# version1_4.net
KiCad netlist of a schematic drawn in EAGLE
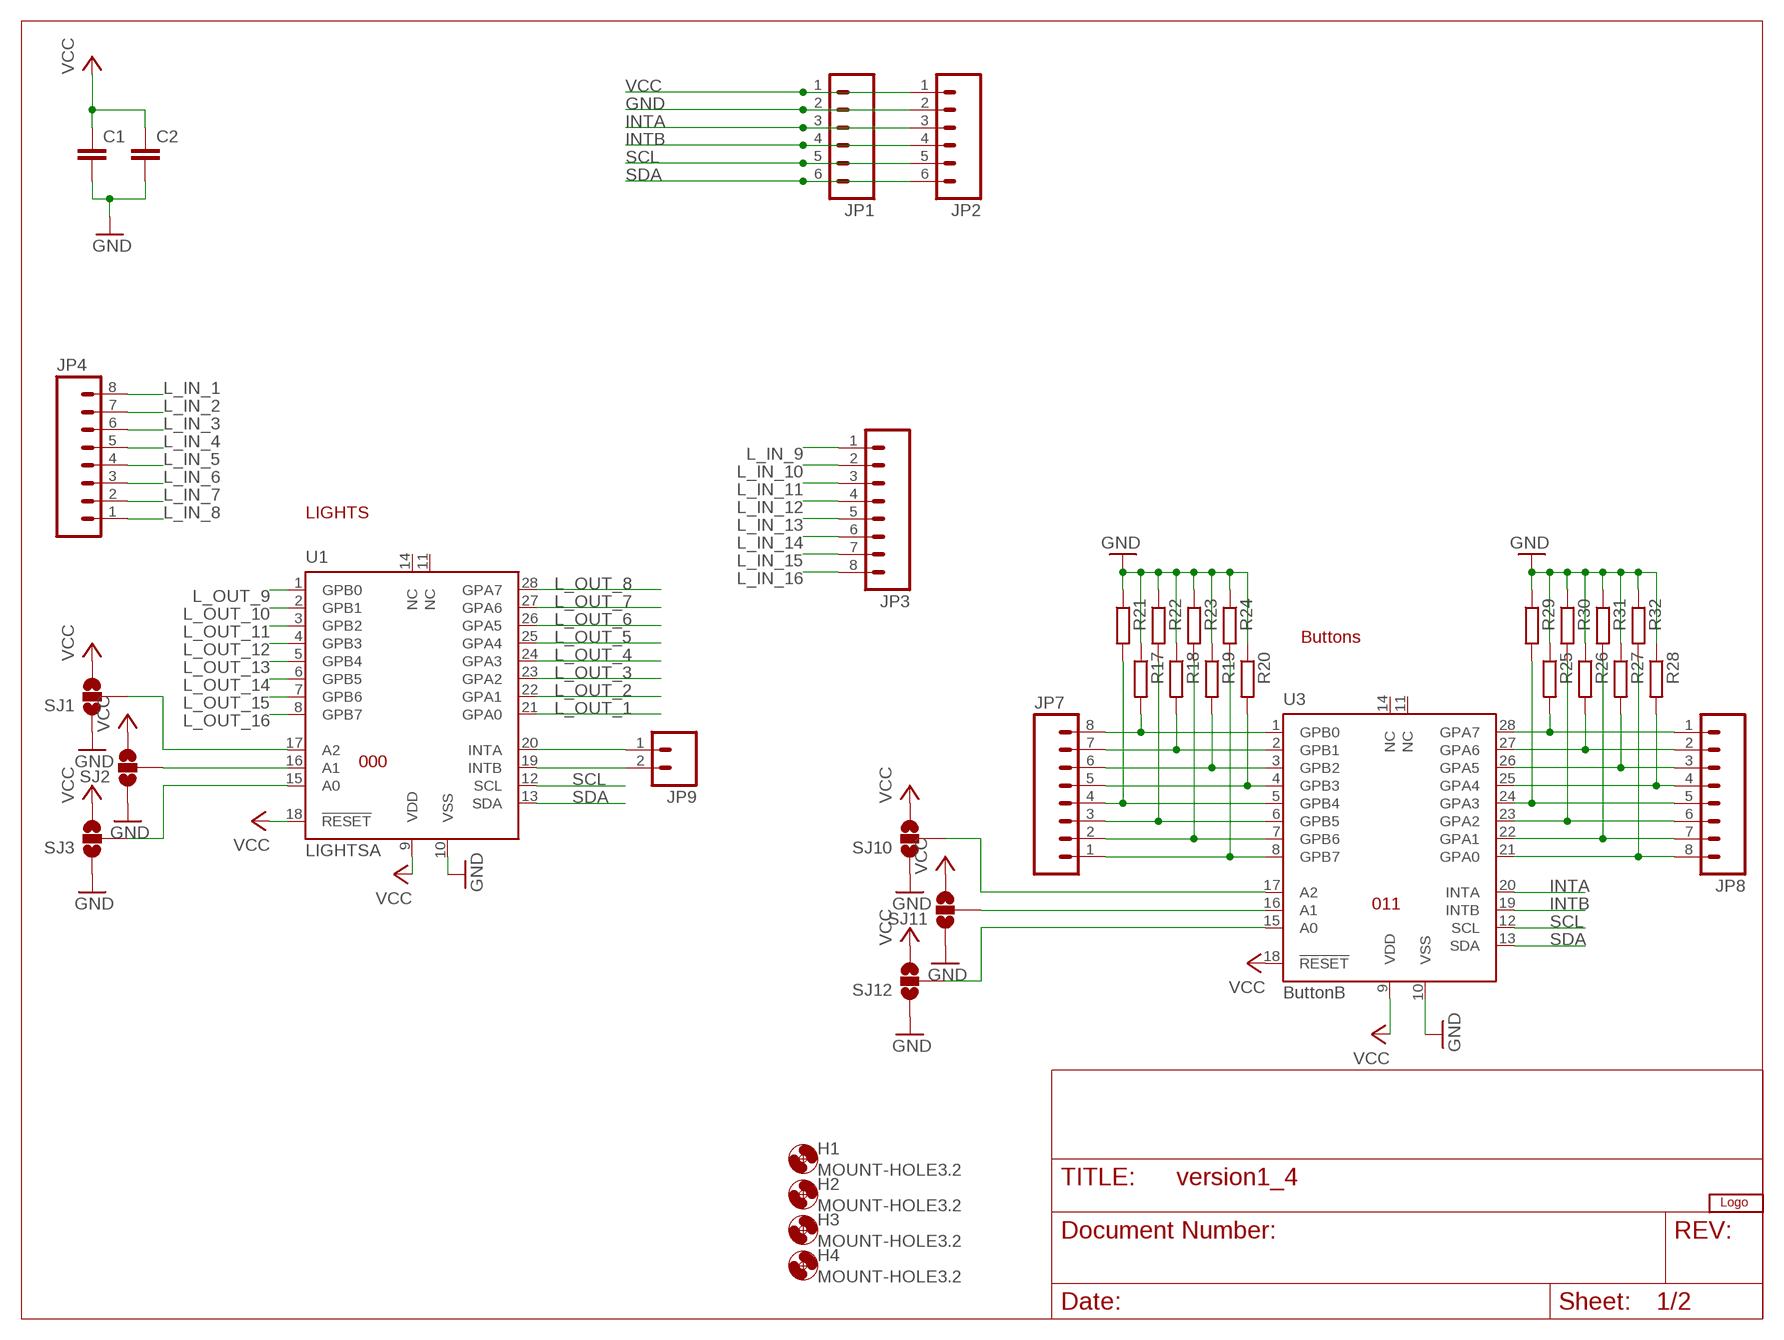
[diagram p0: schematic, sheet 1]
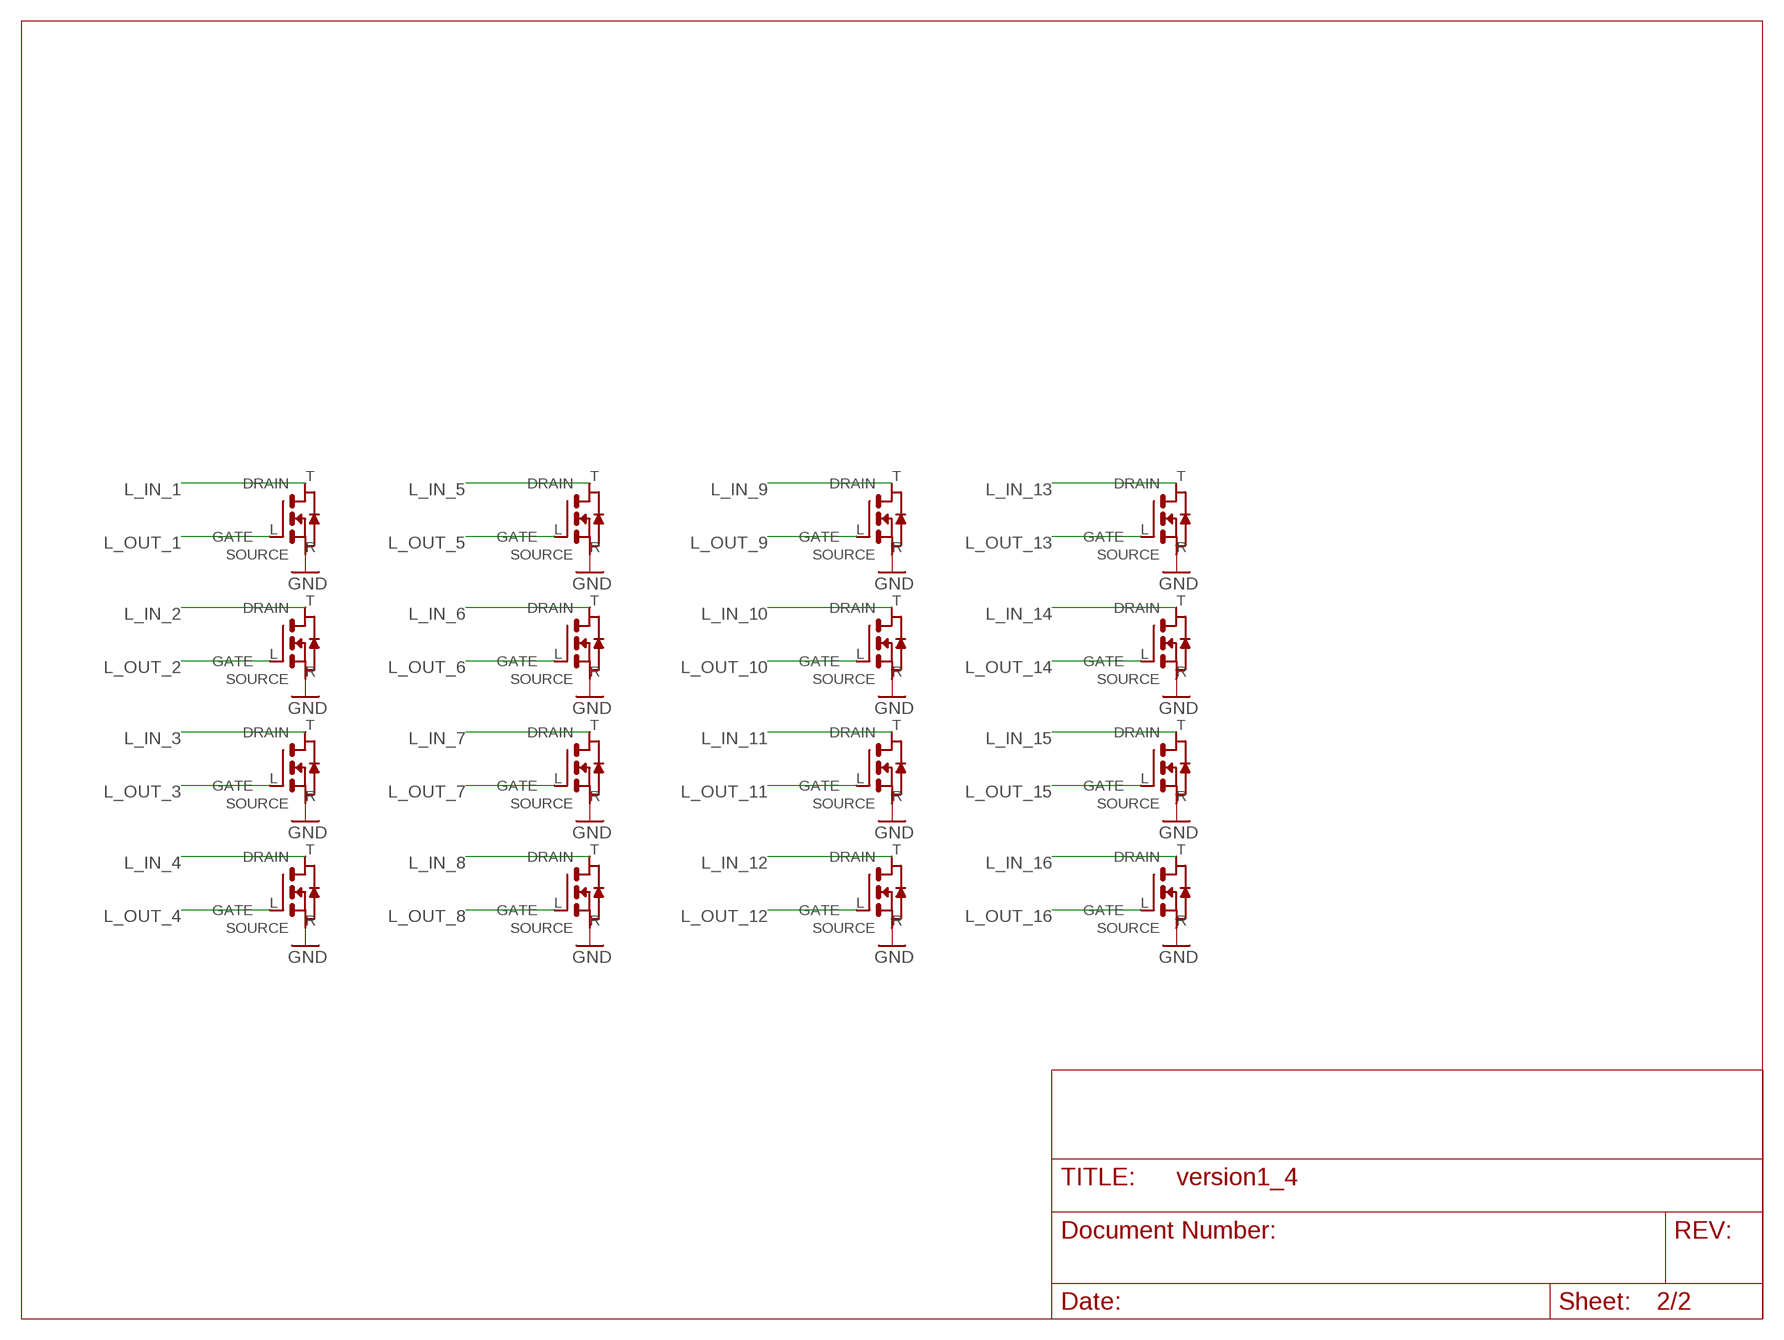
[diagram p1: schematic, sheet 2]

(export (version "E")
  (design (tool "Eeschema 10.0.6"))
  (components
    (comp (ref "C1")
      (value "C-EUC0805")
      (footprint "eagle-import:C0805")
      (libsource (lib "eagle-import") (part "C-EUC0805"))
    )
    (comp (ref "C2")
      (value "C-EUC0805")
      (footprint "eagle-import:C0805")
      (libsource (lib "eagle-import") (part "C-EUC0805"))
    )
    (comp (ref "H1")
      (value "MOUNT-HOLE3.2")
      (footprint "eagle-import:3,2")
      (libsource (lib "eagle-import") (part "MOUNT-HOLE3.2"))
    )
    (comp (ref "H2")
      (value "MOUNT-HOLE3.2")
      (footprint "eagle-import:3,2")
      (libsource (lib "eagle-import") (part "MOUNT-HOLE3.2"))
    )
    (comp (ref "H3")
      (value "MOUNT-HOLE3.2")
      (footprint "eagle-import:3,2")
      (libsource (lib "eagle-import") (part "MOUNT-HOLE3.2"))
    )
    (comp (ref "H4")
      (value "MOUNT-HOLE3.2")
      (footprint "eagle-import:3,2")
      (libsource (lib "eagle-import") (part "MOUNT-HOLE3.2"))
    )
    (comp (ref "JP1")
      (value "M06LOCK")
      (footprint "eagle-import:1X06_LOCK")
      (libsource (lib "eagle-import") (part "M06LOCK"))
    )
    (comp (ref "JP2")
      (value "M06LOCK")
      (footprint "eagle-import:1X06_LOCK")
      (libsource (lib "eagle-import") (part "M06LOCK"))
    )
    (comp (ref "JP3")
      (value "M08LOCK")
      (footprint "eagle-import:1X08_LOCK")
      (libsource (lib "eagle-import") (part "M08LOCK"))
    )
    (comp (ref "JP4")
      (value "M08LOCK")
      (footprint "eagle-import:1X08_LOCK")
      (libsource (lib "eagle-import") (part "M08LOCK"))
    )
    (comp (ref "JP7")
      (value "M08LOCK")
      (footprint "eagle-import:1X08_LOCK")
      (libsource (lib "eagle-import") (part "M08LOCK"))
    )
    (comp (ref "JP8")
      (value "M08LOCK")
      (footprint "eagle-import:1X08_LOCK")
      (libsource (lib "eagle-import") (part "M08LOCK"))
    )
    (comp (ref "JP9")
      (value "M021X02_NO_SILK")
      (footprint "eagle-import:1X02_NO_SILK")
      (libsource (lib "eagle-import") (part "M021X02_NO_SILK"))
    )
    (comp (ref "R17")
      (value "R-EU_R0805")
      (footprint "eagle-import:R0805")
      (libsource (lib "eagle-import") (part "R-EU_R0805"))
    )
    (comp (ref "R18")
      (value "R-EU_R0805")
      (footprint "eagle-import:R0805")
      (libsource (lib "eagle-import") (part "R-EU_R0805"))
    )
    (comp (ref "R19")
      (value "R-EU_R0805")
      (footprint "eagle-import:R0805")
      (libsource (lib "eagle-import") (part "R-EU_R0805"))
    )
    (comp (ref "R20")
      (value "R-EU_R0805")
      (footprint "eagle-import:R0805")
      (libsource (lib "eagle-import") (part "R-EU_R0805"))
    )
    (comp (ref "R21")
      (value "R-EU_R0805")
      (footprint "eagle-import:R0805")
      (libsource (lib "eagle-import") (part "R-EU_R0805"))
    )
    (comp (ref "R22")
      (value "R-EU_R0805")
      (footprint "eagle-import:R0805")
      (libsource (lib "eagle-import") (part "R-EU_R0805"))
    )
    (comp (ref "R23")
      (value "R-EU_R0805")
      (footprint "eagle-import:R0805")
      (libsource (lib "eagle-import") (part "R-EU_R0805"))
    )
    (comp (ref "R24")
      (value "R-EU_R0805")
      (footprint "eagle-import:R0805")
      (libsource (lib "eagle-import") (part "R-EU_R0805"))
    )
    (comp (ref "R25")
      (value "R-EU_R0805")
      (footprint "eagle-import:R0805")
      (libsource (lib "eagle-import") (part "R-EU_R0805"))
    )
    (comp (ref "R26")
      (value "R-EU_R0805")
      (footprint "eagle-import:R0805")
      (libsource (lib "eagle-import") (part "R-EU_R0805"))
    )
    (comp (ref "R27")
      (value "R-EU_R0805")
      (footprint "eagle-import:R0805")
      (libsource (lib "eagle-import") (part "R-EU_R0805"))
    )
    (comp (ref "R28")
      (value "R-EU_R0805")
      (footprint "eagle-import:R0805")
      (libsource (lib "eagle-import") (part "R-EU_R0805"))
    )
    (comp (ref "R29")
      (value "R-EU_R0805")
      (footprint "eagle-import:R0805")
      (libsource (lib "eagle-import") (part "R-EU_R0805"))
    )
    (comp (ref "R30")
      (value "R-EU_R0805")
      (footprint "eagle-import:R0805")
      (libsource (lib "eagle-import") (part "R-EU_R0805"))
    )
    (comp (ref "R31")
      (value "R-EU_R0805")
      (footprint "eagle-import:R0805")
      (libsource (lib "eagle-import") (part "R-EU_R0805"))
    )
    (comp (ref "R32")
      (value "R-EU_R0805")
      (footprint "eagle-import:R0805")
      (libsource (lib "eagle-import") (part "R-EU_R0805"))
    )
    (comp (ref "SJ1")
      (value "SOLDERJUMPER_2WAY-OLDS")
      (footprint "eagle-import:SJ_3")
      (libsource (lib "eagle-import") (part "SOLDERJUMPER_2WAY-OLDS"))
    )
    (comp (ref "SJ2")
      (value "SOLDERJUMPER_2WAY-OLDS")
      (footprint "eagle-import:SJ_3")
      (libsource (lib "eagle-import") (part "SOLDERJUMPER_2WAY-OLDS"))
    )
    (comp (ref "SJ3")
      (value "SOLDERJUMPER_2WAY-OLDS")
      (footprint "eagle-import:SJ_3")
      (libsource (lib "eagle-import") (part "SOLDERJUMPER_2WAY-OLDS"))
    )
    (comp (ref "SJ10")
      (value "SOLDERJUMPER_2WAY-OLDS")
      (footprint "eagle-import:SJ_3")
      (libsource (lib "eagle-import") (part "SOLDERJUMPER_2WAY-OLDS"))
    )
    (comp (ref "SJ11")
      (value "SOLDERJUMPER_2WAY-OLDS")
      (footprint "eagle-import:SJ_3")
      (libsource (lib "eagle-import") (part "SOLDERJUMPER_2WAY-OLDS"))
    )
    (comp (ref "SJ12")
      (value "SOLDERJUMPER_2WAY-OLDS")
      (footprint "eagle-import:SJ_3")
      (libsource (lib "eagle-import") (part "SOLDERJUMPER_2WAY-OLDS"))
    )
    (comp (ref "U$1")
      (value "BUNNYLOGOCALVIN2")
      (footprint "eagle-import:CALVIN2")
      (libsource (lib "eagle-import") (part "BUNNYLOGOCALVIN2"))
    )
    (comp (ref "U1")
      (value "LIGHTSA")
      (footprint "eagle-import:MCP23017A")
      (libsource (lib "eagle-import") (part "MCP23017A"))
    )
    (comp (ref "U3")
      (value "ButtonB")
      (footprint "eagle-import:MCP23017A")
      (libsource (lib "eagle-import") (part "MCP23017A"))
    )
    (comp (ref "Q1")
      (value "DMG2302U")
      (footprint "eagle-import:SOT23-3A")
      (libsource (lib "eagle-import") (part "DMG2302U"))
    )
    (comp (ref "Q2")
      (value "DMG2302U")
      (footprint "eagle-import:SOT23-3A")
      (libsource (lib "eagle-import") (part "DMG2302U"))
    )
    (comp (ref "Q3")
      (value "DMG2302U")
      (footprint "eagle-import:SOT23-3A")
      (libsource (lib "eagle-import") (part "DMG2302U"))
    )
    (comp (ref "Q4")
      (value "DMG2302U")
      (footprint "eagle-import:SOT23-3A")
      (libsource (lib "eagle-import") (part "DMG2302U"))
    )
    (comp (ref "Q5")
      (value "DMG2302U")
      (footprint "eagle-import:SOT23-3A")
      (libsource (lib "eagle-import") (part "DMG2302U"))
    )
    (comp (ref "Q6")
      (value "DMG2302U")
      (footprint "eagle-import:SOT23-3A")
      (libsource (lib "eagle-import") (part "DMG2302U"))
    )
    (comp (ref "Q7")
      (value "DMG2302U")
      (footprint "eagle-import:SOT23-3A")
      (libsource (lib "eagle-import") (part "DMG2302U"))
    )
    (comp (ref "Q8")
      (value "DMG2302U")
      (footprint "eagle-import:SOT23-3A")
      (libsource (lib "eagle-import") (part "DMG2302U"))
    )
    (comp (ref "Q9")
      (value "DMG2302U")
      (footprint "eagle-import:SOT23-3A")
      (libsource (lib "eagle-import") (part "DMG2302U"))
    )
    (comp (ref "Q10")
      (value "DMG2302U")
      (footprint "eagle-import:SOT23-3A")
      (libsource (lib "eagle-import") (part "DMG2302U"))
    )
    (comp (ref "Q11")
      (value "DMG2302U")
      (footprint "eagle-import:SOT23-3A")
      (libsource (lib "eagle-import") (part "DMG2302U"))
    )
    (comp (ref "Q12")
      (value "DMG2302U")
      (footprint "eagle-import:SOT23-3A")
      (libsource (lib "eagle-import") (part "DMG2302U"))
    )
    (comp (ref "Q13")
      (value "DMG2302U")
      (footprint "eagle-import:SOT23-3A")
      (libsource (lib "eagle-import") (part "DMG2302U"))
    )
    (comp (ref "Q14")
      (value "DMG2302U")
      (footprint "eagle-import:SOT23-3A")
      (libsource (lib "eagle-import") (part "DMG2302U"))
    )
    (comp (ref "Q15")
      (value "DMG2302U")
      (footprint "eagle-import:SOT23-3A")
      (libsource (lib "eagle-import") (part "DMG2302U"))
    )
    (comp (ref "Q16")
      (value "DMG2302U")
      (footprint "eagle-import:SOT23-3A")
      (libsource (lib "eagle-import") (part "DMG2302U"))
    )
  )
  (nets
    (net (code "1") (name "GND") (class "Default")
      (node (ref "C1") (pin "2") (pinfunction "2_2") (pintype "passive"))
      (node (ref "C2") (pin "2") (pinfunction "2_2") (pintype "passive"))
      (node (ref "JP1") (pin "2") (pinfunction "2_2") (pintype "passive"))
      (node (ref "JP2") (pin "2") (pinfunction "2_2") (pintype "passive"))
      (node (ref "Q1") (pin "R") (pinfunction "SOURCE_R") (pintype "bidirectional"))
      (node (ref "Q10") (pin "R") (pinfunction "SOURCE_R") (pintype "bidirectional"))
      (node (ref "Q11") (pin "R") (pinfunction "SOURCE_R") (pintype "bidirectional"))
      (node (ref "Q12") (pin "R") (pinfunction "SOURCE_R") (pintype "bidirectional"))
      (node (ref "Q13") (pin "R") (pinfunction "SOURCE_R") (pintype "bidirectional"))
      (node (ref "Q14") (pin "R") (pinfunction "SOURCE_R") (pintype "bidirectional"))
      (node (ref "Q15") (pin "R") (pinfunction "SOURCE_R") (pintype "bidirectional"))
      (node (ref "Q16") (pin "R") (pinfunction "SOURCE_R") (pintype "bidirectional"))
      (node (ref "Q2") (pin "R") (pinfunction "SOURCE_R") (pintype "bidirectional"))
      (node (ref "Q3") (pin "R") (pinfunction "SOURCE_R") (pintype "bidirectional"))
      (node (ref "Q4") (pin "R") (pinfunction "SOURCE_R") (pintype "bidirectional"))
      (node (ref "Q5") (pin "R") (pinfunction "SOURCE_R") (pintype "bidirectional"))
      (node (ref "Q6") (pin "R") (pinfunction "SOURCE_R") (pintype "bidirectional"))
      (node (ref "Q7") (pin "R") (pinfunction "SOURCE_R") (pintype "bidirectional"))
      (node (ref "Q8") (pin "R") (pinfunction "SOURCE_R") (pintype "bidirectional"))
      (node (ref "Q9") (pin "R") (pinfunction "SOURCE_R") (pintype "bidirectional"))
      (node (ref "R17") (pin "1") (pinfunction "1_1") (pintype "passive"))
      (node (ref "R18") (pin "1") (pinfunction "1_1") (pintype "passive"))
      (node (ref "R19") (pin "1") (pinfunction "1_1") (pintype "passive"))
      (node (ref "R20") (pin "1") (pinfunction "1_1") (pintype "passive"))
      (node (ref "R21") (pin "1") (pinfunction "1_1") (pintype "passive"))
      (node (ref "R22") (pin "1") (pinfunction "1_1") (pintype "passive"))
      (node (ref "R23") (pin "1") (pinfunction "1_1") (pintype "passive"))
      (node (ref "R24") (pin "1") (pinfunction "1_1") (pintype "passive"))
      (node (ref "R25") (pin "1") (pinfunction "1_1") (pintype "passive"))
      (node (ref "R26") (pin "1") (pinfunction "1_1") (pintype "passive"))
      (node (ref "R27") (pin "1") (pinfunction "1_1") (pintype "passive"))
      (node (ref "R28") (pin "1") (pinfunction "1_1") (pintype "passive"))
      (node (ref "R29") (pin "1") (pinfunction "1_1") (pintype "passive"))
      (node (ref "R30") (pin "1") (pinfunction "1_1") (pintype "passive"))
      (node (ref "R31") (pin "1") (pinfunction "1_1") (pintype "passive"))
      (node (ref "R32") (pin "1") (pinfunction "1_1") (pintype "passive"))
      (node (ref "SJ1") (pin "1") (pinfunction "1_1") (pintype "passive"))
      (node (ref "SJ10") (pin "1") (pinfunction "1_1") (pintype "passive"))
      (node (ref "SJ11") (pin "1") (pinfunction "1_1") (pintype "passive"))
      (node (ref "SJ12") (pin "1") (pinfunction "1_1") (pintype "passive"))
      (node (ref "SJ2") (pin "1") (pinfunction "1_1") (pintype "passive"))
      (node (ref "SJ3") (pin "1") (pinfunction "1_1") (pintype "passive"))
      (node (ref "U1") (pin "10") (pinfunction "VSS_10") (pintype "power_in"))
      (node (ref "U3") (pin "10") (pinfunction "VSS_10") (pintype "power_in"))
    )
    (net (code "2") (name "INTA") (class "Default")
      (node (ref "JP1") (pin "3") (pinfunction "3_3") (pintype "passive"))
      (node (ref "JP2") (pin "3") (pinfunction "3_3") (pintype "passive"))
      (node (ref "U3") (pin "20") (pinfunction "INTA_20") (pintype "bidirectional"))
    )
    (net (code "3") (name "INTB") (class "Default")
      (node (ref "JP1") (pin "4") (pinfunction "4_4") (pintype "passive"))
      (node (ref "JP2") (pin "4") (pinfunction "4_4") (pintype "passive"))
      (node (ref "U3") (pin "19") (pinfunction "INTB_19") (pintype "bidirectional"))
    )
    (net (code "4") (name "L_IN_1") (class "Default")
      (node (ref "JP4") (pin "8") (pinfunction "8_8") (pintype "passive"))
      (node (ref "Q2") (pin "T") (pinfunction "DRAIN_T") (pintype "bidirectional"))
    )
    (net (code "5") (name "L_IN_2") (class "Default")
      (node (ref "JP4") (pin "7") (pinfunction "7_7") (pintype "passive"))
      (node (ref "Q1") (pin "T") (pinfunction "DRAIN_T") (pintype "bidirectional"))
    )
    (net (code "6") (name "L_IN_3") (class "Default")
      (node (ref "JP4") (pin "6") (pinfunction "6_6") (pintype "passive"))
      (node (ref "Q3") (pin "T") (pinfunction "DRAIN_T") (pintype "bidirectional"))
    )
    (net (code "7") (name "L_IN_4") (class "Default")
      (node (ref "JP4") (pin "5") (pinfunction "5_5") (pintype "passive"))
      (node (ref "Q4") (pin "T") (pinfunction "DRAIN_T") (pintype "bidirectional"))
    )
    (net (code "8") (name "L_IN_5") (class "Default")
      (node (ref "JP4") (pin "4") (pinfunction "4_4") (pintype "passive"))
      (node (ref "Q5") (pin "T") (pinfunction "DRAIN_T") (pintype "bidirectional"))
    )
    (net (code "9") (name "L_IN_6") (class "Default")
      (node (ref "JP4") (pin "3") (pinfunction "3_3") (pintype "passive"))
      (node (ref "Q6") (pin "T") (pinfunction "DRAIN_T") (pintype "bidirectional"))
    )
    (net (code "10") (name "L_IN_7") (class "Default")
      (node (ref "JP4") (pin "2") (pinfunction "2_2") (pintype "passive"))
      (node (ref "Q7") (pin "T") (pinfunction "DRAIN_T") (pintype "bidirectional"))
    )
    (net (code "11") (name "L_IN_8") (class "Default")
      (node (ref "JP4") (pin "1") (pinfunction "1_1") (pintype "passive"))
      (node (ref "Q8") (pin "T") (pinfunction "DRAIN_T") (pintype "bidirectional"))
    )
    (net (code "12") (name "L_IN_9") (class "Default")
      (node (ref "JP3") (pin "1") (pinfunction "1_1") (pintype "passive"))
      (node (ref "Q9") (pin "T") (pinfunction "DRAIN_T") (pintype "bidirectional"))
    )
    (net (code "13") (name "L_IN_10") (class "Default")
      (node (ref "JP3") (pin "2") (pinfunction "2_2") (pintype "passive"))
      (node (ref "Q10") (pin "T") (pinfunction "DRAIN_T") (pintype "bidirectional"))
    )
    (net (code "14") (name "L_IN_11") (class "Default")
      (node (ref "JP3") (pin "3") (pinfunction "3_3") (pintype "passive"))
      (node (ref "Q11") (pin "T") (pinfunction "DRAIN_T") (pintype "bidirectional"))
    )
    (net (code "15") (name "L_IN_12") (class "Default")
      (node (ref "JP3") (pin "4") (pinfunction "4_4") (pintype "passive"))
      (node (ref "Q12") (pin "T") (pinfunction "DRAIN_T") (pintype "bidirectional"))
    )
    (net (code "16") (name "L_IN_13") (class "Default")
      (node (ref "JP3") (pin "5") (pinfunction "5_5") (pintype "passive"))
      (node (ref "Q13") (pin "T") (pinfunction "DRAIN_T") (pintype "bidirectional"))
    )
    (net (code "17") (name "L_IN_14") (class "Default")
      (node (ref "JP3") (pin "6") (pinfunction "6_6") (pintype "passive"))
      (node (ref "Q14") (pin "T") (pinfunction "DRAIN_T") (pintype "bidirectional"))
    )
    (net (code "18") (name "L_IN_15") (class "Default")
      (node (ref "JP3") (pin "7") (pinfunction "7_7") (pintype "passive"))
      (node (ref "Q15") (pin "T") (pinfunction "DRAIN_T") (pintype "bidirectional"))
    )
    (net (code "19") (name "L_IN_16") (class "Default")
      (node (ref "JP3") (pin "8") (pinfunction "8_8") (pintype "passive"))
      (node (ref "Q16") (pin "T") (pinfunction "DRAIN_T") (pintype "bidirectional"))
    )
    (net (code "20") (name "L_OUT_1") (class "Default")
      (node (ref "Q2") (pin "L") (pinfunction "GATE_L") (pintype "bidirectional"))
      (node (ref "U1") (pin "21") (pinfunction "GPA0_21") (pintype "bidirectional"))
    )
    (net (code "21") (name "L_OUT_2") (class "Default")
      (node (ref "Q1") (pin "L") (pinfunction "GATE_L") (pintype "bidirectional"))
      (node (ref "U1") (pin "22") (pinfunction "GPA1_22") (pintype "bidirectional"))
    )
    (net (code "22") (name "L_OUT_3") (class "Default")
      (node (ref "Q3") (pin "L") (pinfunction "GATE_L") (pintype "bidirectional"))
      (node (ref "U1") (pin "23") (pinfunction "GPA2_23") (pintype "bidirectional"))
    )
    (net (code "23") (name "L_OUT_4") (class "Default")
      (node (ref "Q4") (pin "L") (pinfunction "GATE_L") (pintype "bidirectional"))
      (node (ref "U1") (pin "24") (pinfunction "GPA3_24") (pintype "bidirectional"))
    )
    (net (code "24") (name "L_OUT_5") (class "Default")
      (node (ref "Q5") (pin "L") (pinfunction "GATE_L") (pintype "bidirectional"))
      (node (ref "U1") (pin "25") (pinfunction "GPA4_25") (pintype "bidirectional"))
    )
    (net (code "25") (name "L_OUT_6") (class "Default")
      (node (ref "Q6") (pin "L") (pinfunction "GATE_L") (pintype "bidirectional"))
      (node (ref "U1") (pin "26") (pinfunction "GPA5_26") (pintype "bidirectional"))
    )
    (net (code "26") (name "L_OUT_7") (class "Default")
      (node (ref "Q7") (pin "L") (pinfunction "GATE_L") (pintype "bidirectional"))
      (node (ref "U1") (pin "27") (pinfunction "GPA6_27") (pintype "bidirectional"))
    )
    (net (code "27") (name "L_OUT_8") (class "Default")
      (node (ref "Q8") (pin "L") (pinfunction "GATE_L") (pintype "bidirectional"))
      (node (ref "U1") (pin "28") (pinfunction "GPA7_28") (pintype "bidirectional"))
    )
    (net (code "28") (name "L_OUT_9") (class "Default")
      (node (ref "Q9") (pin "L") (pinfunction "GATE_L") (pintype "bidirectional"))
      (node (ref "U1") (pin "1") (pinfunction "GPB0_1") (pintype "bidirectional"))
    )
    (net (code "29") (name "L_OUT_10") (class "Default")
      (node (ref "Q10") (pin "L") (pinfunction "GATE_L") (pintype "bidirectional"))
      (node (ref "U1") (pin "2") (pinfunction "GPB1_2") (pintype "bidirectional"))
    )
    (net (code "30") (name "L_OUT_11") (class "Default")
      (node (ref "Q11") (pin "L") (pinfunction "GATE_L") (pintype "bidirectional"))
      (node (ref "U1") (pin "3") (pinfunction "GPB2_3") (pintype "bidirectional"))
    )
    (net (code "31") (name "L_OUT_12") (class "Default")
      (node (ref "Q12") (pin "L") (pinfunction "GATE_L") (pintype "bidirectional"))
      (node (ref "U1") (pin "4") (pinfunction "GPB3_4") (pintype "bidirectional"))
    )
    (net (code "32") (name "L_OUT_13") (class "Default")
      (node (ref "Q13") (pin "L") (pinfunction "GATE_L") (pintype "bidirectional"))
      (node (ref "U1") (pin "5") (pinfunction "GPB4_5") (pintype "bidirectional"))
    )
    (net (code "33") (name "L_OUT_14") (class "Default")
      (node (ref "Q14") (pin "L") (pinfunction "GATE_L") (pintype "bidirectional"))
      (node (ref "U1") (pin "6") (pinfunction "GPB5_6") (pintype "bidirectional"))
    )
    (net (code "34") (name "L_OUT_15") (class "Default")
      (node (ref "Q15") (pin "L") (pinfunction "GATE_L") (pintype "bidirectional"))
      (node (ref "U1") (pin "7") (pinfunction "GPB6_7") (pintype "bidirectional"))
    )
    (net (code "35") (name "L_OUT_16") (class "Default")
      (node (ref "Q16") (pin "L") (pinfunction "GATE_L") (pintype "bidirectional"))
      (node (ref "U1") (pin "8") (pinfunction "GPB7_8") (pintype "bidirectional"))
    )
    (net (code "36") (name "Net-(U1-A0)") (class "Default")
      (node (ref "SJ3") (pin "2") (pinfunction "2_2") (pintype "passive"))
      (node (ref "U1") (pin "15") (pinfunction "A0_15") (pintype "bidirectional"))
    )
    (net (code "37") (name "Net-(U1-A1)") (class "Default")
      (node (ref "SJ2") (pin "2") (pinfunction "2_2") (pintype "passive"))
      (node (ref "U1") (pin "16") (pinfunction "A1_16") (pintype "bidirectional"))
    )
    (net (code "38") (name "Net-(U1-A2)") (class "Default")
      (node (ref "SJ1") (pin "2") (pinfunction "2_2") (pintype "passive"))
      (node (ref "U1") (pin "17") (pinfunction "A2_17") (pintype "bidirectional"))
    )
    (net (code "39") (name "Net-(U1-INTA)") (class "Default")
      (node (ref "JP9") (pin "1") (pinfunction "1_1") (pintype "passive"))
      (node (ref "U1") (pin "20") (pinfunction "INTA_20") (pintype "bidirectional"))
    )
    (net (code "40") (name "Net-(U1-INTB)") (class "Default")
      (node (ref "JP9") (pin "2") (pinfunction "2_2") (pintype "passive"))
      (node (ref "U1") (pin "19") (pinfunction "INTB_19") (pintype "bidirectional"))
    )
    (net (code "41") (name "Net-(U3-A0)") (class "Default")
      (node (ref "SJ12") (pin "2") (pinfunction "2_2") (pintype "passive"))
      (node (ref "U3") (pin "15") (pinfunction "A0_15") (pintype "bidirectional"))
    )
    (net (code "42") (name "Net-(U3-A1)") (class "Default")
      (node (ref "SJ11") (pin "2") (pinfunction "2_2") (pintype "passive"))
      (node (ref "U3") (pin "16") (pinfunction "A1_16") (pintype "bidirectional"))
    )
    (net (code "43") (name "Net-(U3-A2)") (class "Default")
      (node (ref "SJ10") (pin "2") (pinfunction "2_2") (pintype "passive"))
      (node (ref "U3") (pin "17") (pinfunction "A2_17") (pintype "bidirectional"))
    )
    (net (code "44") (name "Net-(U3-GPA0)") (class "Default")
      (node (ref "JP8") (pin "8") (pinfunction "8_8") (pintype "passive"))
      (node (ref "R32") (pin "2") (pinfunction "2_2") (pintype "passive"))
      (node (ref "U3") (pin "21") (pinfunction "GPA0_21") (pintype "bidirectional"))
    )
    (net (code "45") (name "Net-(U3-GPA1)") (class "Default")
      (node (ref "JP8") (pin "7") (pinfunction "7_7") (pintype "passive"))
      (node (ref "R31") (pin "2") (pinfunction "2_2") (pintype "passive"))
      (node (ref "U3") (pin "22") (pinfunction "GPA1_22") (pintype "bidirectional"))
    )
    (net (code "46") (name "Net-(U3-GPA2)") (class "Default")
      (node (ref "JP8") (pin "6") (pinfunction "6_6") (pintype "passive"))
      (node (ref "R30") (pin "2") (pinfunction "2_2") (pintype "passive"))
      (node (ref "U3") (pin "23") (pinfunction "GPA2_23") (pintype "bidirectional"))
    )
    (net (code "47") (name "Net-(U3-GPA3)") (class "Default")
      (node (ref "JP8") (pin "5") (pinfunction "5_5") (pintype "passive"))
      (node (ref "R29") (pin "2") (pinfunction "2_2") (pintype "passive"))
      (node (ref "U3") (pin "24") (pinfunction "GPA3_24") (pintype "bidirectional"))
    )
    (net (code "48") (name "Net-(U3-GPA4)") (class "Default")
      (node (ref "JP8") (pin "4") (pinfunction "4_4") (pintype "passive"))
      (node (ref "R28") (pin "2") (pinfunction "2_2") (pintype "passive"))
      (node (ref "U3") (pin "25") (pinfunction "GPA4_25") (pintype "bidirectional"))
    )
    (net (code "49") (name "Net-(U3-GPA5)") (class "Default")
      (node (ref "JP8") (pin "3") (pinfunction "3_3") (pintype "passive"))
      (node (ref "R27") (pin "2") (pinfunction "2_2") (pintype "passive"))
      (node (ref "U3") (pin "26") (pinfunction "GPA5_26") (pintype "bidirectional"))
    )
    (net (code "50") (name "Net-(U3-GPA6)") (class "Default")
      (node (ref "JP8") (pin "2") (pinfunction "2_2") (pintype "passive"))
      (node (ref "R26") (pin "2") (pinfunction "2_2") (pintype "passive"))
      (node (ref "U3") (pin "27") (pinfunction "GPA6_27") (pintype "bidirectional"))
    )
    (net (code "51") (name "Net-(U3-GPA7)") (class "Default")
      (node (ref "JP8") (pin "1") (pinfunction "1_1") (pintype "passive"))
      (node (ref "R25") (pin "2") (pinfunction "2_2") (pintype "passive"))
      (node (ref "U3") (pin "28") (pinfunction "GPA7_28") (pintype "bidirectional"))
    )
    (net (code "52") (name "Net-(U3-GPB0)") (class "Default")
      (node (ref "JP7") (pin "8") (pinfunction "8_8") (pintype "passive"))
      (node (ref "R17") (pin "2") (pinfunction "2_2") (pintype "passive"))
      (node (ref "U3") (pin "1") (pinfunction "GPB0_1") (pintype "bidirectional"))
    )
    (net (code "53") (name "Net-(U3-GPB1)") (class "Default")
      (node (ref "JP7") (pin "7") (pinfunction "7_7") (pintype "passive"))
      (node (ref "R18") (pin "2") (pinfunction "2_2") (pintype "passive"))
      (node (ref "U3") (pin "2") (pinfunction "GPB1_2") (pintype "bidirectional"))
    )
    (net (code "54") (name "Net-(U3-GPB2)") (class "Default")
      (node (ref "JP7") (pin "6") (pinfunction "6_6") (pintype "passive"))
      (node (ref "R19") (pin "2") (pinfunction "2_2") (pintype "passive"))
      (node (ref "U3") (pin "3") (pinfunction "GPB2_3") (pintype "bidirectional"))
    )
    (net (code "55") (name "Net-(U3-GPB3)") (class "Default")
      (node (ref "JP7") (pin "5") (pinfunction "5_5") (pintype "passive"))
      (node (ref "R20") (pin "2") (pinfunction "2_2") (pintype "passive"))
      (node (ref "U3") (pin "4") (pinfunction "GPB3_4") (pintype "bidirectional"))
    )
    (net (code "56") (name "Net-(U3-GPB4)") (class "Default")
      (node (ref "JP7") (pin "4") (pinfunction "4_4") (pintype "passive"))
      (node (ref "R21") (pin "2") (pinfunction "2_2") (pintype "passive"))
      (node (ref "U3") (pin "5") (pinfunction "GPB4_5") (pintype "bidirectional"))
    )
    (net (code "57") (name "Net-(U3-GPB5)") (class "Default")
      (node (ref "JP7") (pin "3") (pinfunction "3_3") (pintype "passive"))
      (node (ref "R22") (pin "2") (pinfunction "2_2") (pintype "passive"))
      (node (ref "U3") (pin "6") (pinfunction "GPB5_6") (pintype "bidirectional"))
    )
    (net (code "58") (name "Net-(U3-GPB6)") (class "Default")
      (node (ref "JP7") (pin "2") (pinfunction "2_2") (pintype "passive"))
      (node (ref "R23") (pin "2") (pinfunction "2_2") (pintype "passive"))
      (node (ref "U3") (pin "7") (pinfunction "GPB6_7") (pintype "bidirectional"))
    )
    (net (code "59") (name "Net-(U3-GPB7)") (class "Default")
      (node (ref "JP7") (pin "1") (pinfunction "1_1") (pintype "passive"))
      (node (ref "R24") (pin "2") (pinfunction "2_2") (pintype "passive"))
      (node (ref "U3") (pin "8") (pinfunction "GPB7_8") (pintype "bidirectional"))
    )
    (net (code "60") (name "SCL") (class "Default")
      (node (ref "JP1") (pin "5") (pinfunction "5_5") (pintype "passive"))
      (node (ref "JP2") (pin "5") (pinfunction "5_5") (pintype "passive"))
      (node (ref "U1") (pin "12") (pinfunction "SCL_12") (pintype "bidirectional"))
      (node (ref "U3") (pin "12") (pinfunction "SCL_12") (pintype "bidirectional"))
    )
    (net (code "61") (name "SDA") (class "Default")
      (node (ref "JP1") (pin "6") (pinfunction "6_6") (pintype "passive"))
      (node (ref "JP2") (pin "6") (pinfunction "6_6") (pintype "passive"))
      (node (ref "U1") (pin "13") (pinfunction "SDA_13") (pintype "bidirectional"))
      (node (ref "U3") (pin "13") (pinfunction "SDA_13") (pintype "bidirectional"))
    )
    (net (code "62") (name "VCC") (class "Default")
      (node (ref "C1") (pin "1") (pinfunction "1_1") (pintype "passive"))
      (node (ref "C2") (pin "1") (pinfunction "1_1") (pintype "passive"))
      (node (ref "JP1") (pin "1") (pinfunction "1_1") (pintype "passive"))
      (node (ref "JP2") (pin "1") (pinfunction "1_1") (pintype "passive"))
      (node (ref "SJ1") (pin "3") (pinfunction "3_3") (pintype "passive"))
      (node (ref "SJ10") (pin "3") (pinfunction "3_3") (pintype "passive"))
      (node (ref "SJ11") (pin "3") (pinfunction "3_3") (pintype "passive"))
      (node (ref "SJ12") (pin "3") (pinfunction "3_3") (pintype "passive"))
      (node (ref "SJ2") (pin "3") (pinfunction "3_3") (pintype "passive"))
      (node (ref "SJ3") (pin "3") (pinfunction "3_3") (pintype "passive"))
      (node (ref "U1") (pin "18") (pinfunction "~{RESET}_18") (pintype "bidirectional"))
      (node (ref "U1") (pin "9") (pinfunction "VDD_9") (pintype "power_in"))
      (node (ref "U3") (pin "18") (pinfunction "~{RESET}_18") (pintype "bidirectional"))
      (node (ref "U3") (pin "9") (pinfunction "VDD_9") (pintype "power_in"))
    )
    (net (code "63") (name "unconnected-(U1-NC-Pad11)") (class "Default")
      (node (ref "U1") (pin "11") (pinfunction "NC_11") (pintype "no_connect"))
    )
    (net (code "64") (name "unconnected-(U1-NC-Pad14)") (class "Default")
      (node (ref "U1") (pin "14") (pinfunction "NC_14") (pintype "no_connect"))
    )
    (net (code "65") (name "unconnected-(U3-NC-Pad11)") (class "Default")
      (node (ref "U3") (pin "11") (pinfunction "NC_11") (pintype "no_connect"))
    )
    (net (code "66") (name "unconnected-(U3-NC-Pad14)") (class "Default")
      (node (ref "U3") (pin "14") (pinfunction "NC_14") (pintype "no_connect"))
    )
  )
)
